# 04_-Connector.net
KiCad netlist of a schematic drawn in Altium Designer
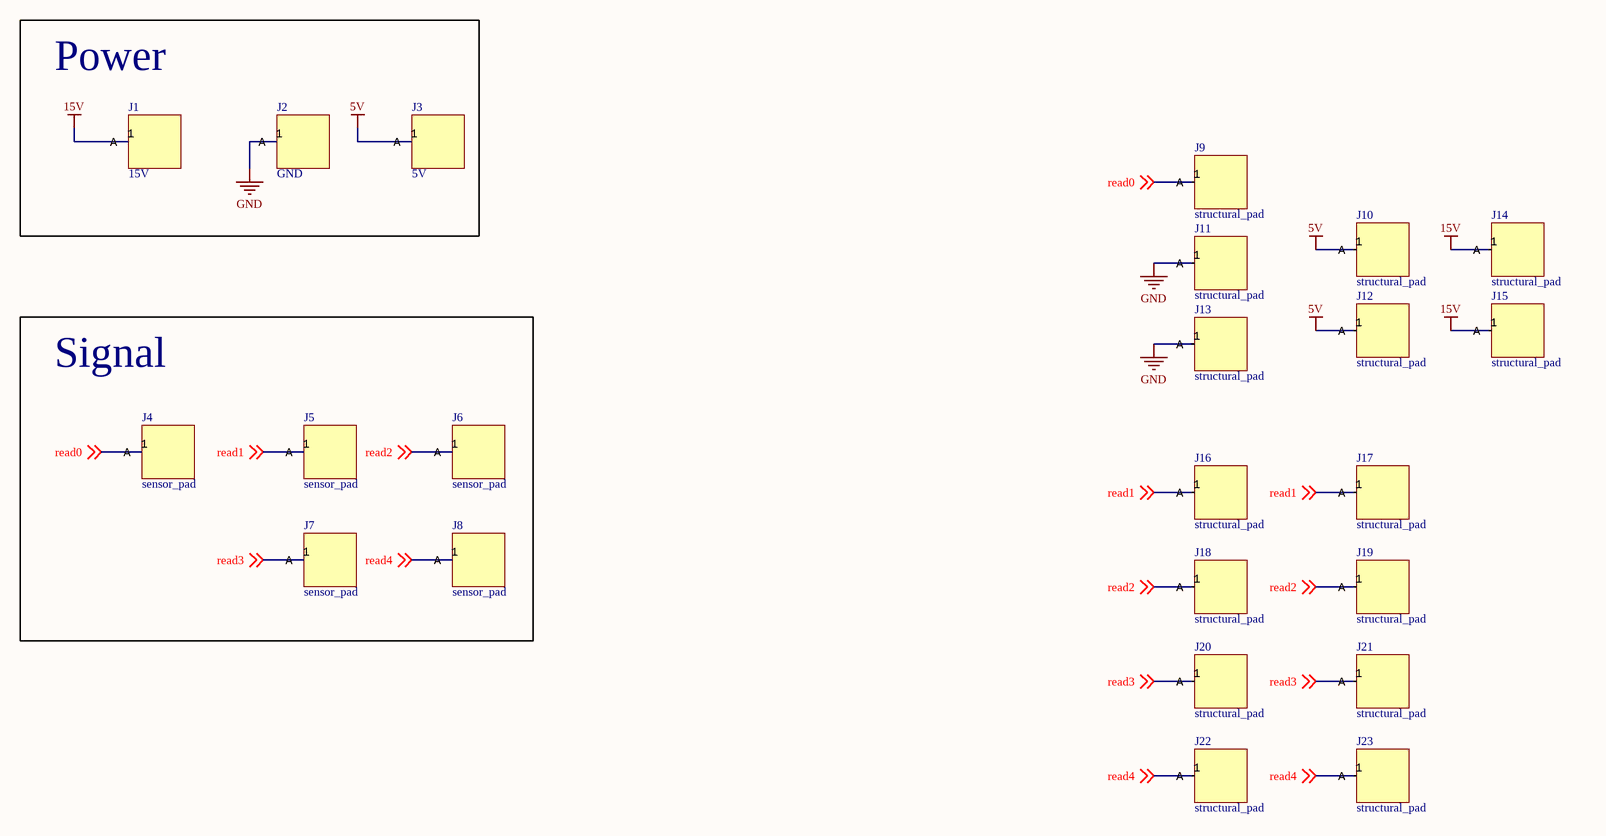
[diagram p0: [04]-Connector.SchDoc]

(export (version "E")
  (design (tool "Eeschema 10.0.6"))
  (components
    (comp (ref "J1") (value "15V") (footprint "PIN") (libsource (lib "Schlib1") (part "15V")))
    (comp (ref "J2") (value "GND") (footprint "PIN") (libsource (lib "Schlib1") (part "GND")))
    (comp (ref "J3") (value "5V") (footprint "PIN") (libsource (lib "Schlib1") (part "15V")))
    (comp (ref "J4") (value "sensor_pad") (footprint "PIN") (libsource (lib "Schlib1") (part "sensor_pad")))
    (comp (ref "J5") (value "sensor_pad") (footprint "PIN") (libsource (lib "Schlib1") (part "sensor_pad")))
    (comp (ref "J6") (value "sensor_pad") (footprint "PIN") (libsource (lib "Schlib1") (part "sensor_pad")))
    (comp (ref "J7") (value "sensor_pad") (footprint "PIN") (libsource (lib "Schlib1") (part "sensor_pad")))
    (comp (ref "J8") (value "sensor_pad") (footprint "PIN") (libsource (lib "Schlib1") (part "sensor_pad")))
    (comp (ref "J9")
      (value "structural_pad")
      (footprint "structural_pad")
      (libsource (lib "Schlib1") (part "structural_pad"))
    )
    (comp (ref "J10")
      (value "structural_pad")
      (footprint "structural_pad")
      (libsource (lib "Schlib1") (part "structural_pad"))
    )
    (comp (ref "J11")
      (value "structural_pad")
      (footprint "structural_pad")
      (libsource (lib "Schlib1") (part "structural_pad"))
    )
    (comp (ref "J12")
      (value "structural_pad")
      (footprint "structural_pad")
      (libsource (lib "Schlib1") (part "structural_pad"))
    )
    (comp (ref "J13")
      (value "structural_pad")
      (footprint "structural_pad")
      (libsource (lib "Schlib1") (part "structural_pad"))
    )
    (comp (ref "J14")
      (value "structural_pad")
      (footprint "structural_pad")
      (libsource (lib "Schlib1") (part "structural_pad"))
    )
    (comp (ref "J15")
      (value "structural_pad")
      (footprint "structural_pad")
      (libsource (lib "Schlib1") (part "structural_pad"))
    )
    (comp (ref "J16")
      (value "structural_pad")
      (footprint "structural_pad")
      (libsource (lib "Schlib1") (part "structural_pad"))
    )
    (comp (ref "J17")
      (value "structural_pad")
      (footprint "structural_pad")
      (libsource (lib "Schlib1") (part "structural_pad"))
    )
    (comp (ref "J18")
      (value "structural_pad")
      (footprint "structural_pad")
      (libsource (lib "Schlib1") (part "structural_pad"))
    )
    (comp (ref "J19")
      (value "structural_pad")
      (footprint "structural_pad")
      (libsource (lib "Schlib1") (part "structural_pad"))
    )
    (comp (ref "J20")
      (value "structural_pad")
      (footprint "structural_pad")
      (libsource (lib "Schlib1") (part "structural_pad"))
    )
    (comp (ref "J21")
      (value "structural_pad")
      (footprint "structural_pad")
      (libsource (lib "Schlib1") (part "structural_pad"))
    )
    (comp (ref "J22")
      (value "structural_pad")
      (footprint "structural_pad")
      (libsource (lib "Schlib1") (part "structural_pad"))
    )
    (comp (ref "J23")
      (value "structural_pad")
      (footprint "structural_pad")
      (libsource (lib "Schlib1") (part "structural_pad"))
    )
  )
  (nets
    (net (code "1") (name "5V") (class "Default")
      (node (ref "J10") (pin "1") (pinfunction "A_1") (pintype "passive"))
      (node (ref "J12") (pin "1") (pinfunction "A_1") (pintype "passive"))
      (node (ref "J3") (pin "1") (pinfunction "A_1") (pintype "passive"))
    )
    (net (code "2") (name "15V") (class "Default")
      (node (ref "J1") (pin "1") (pinfunction "A_1") (pintype "passive"))
      (node (ref "J14") (pin "1") (pinfunction "A_1") (pintype "passive"))
      (node (ref "J15") (pin "1") (pinfunction "A_1") (pintype "passive"))
    )
    (net (code "3") (name "GND") (class "Default")
      (node (ref "J11") (pin "1") (pinfunction "A_1") (pintype "passive"))
      (node (ref "J13") (pin "1") (pinfunction "A_1") (pintype "passive"))
      (node (ref "J2") (pin "1") (pinfunction "A_1") (pintype "passive"))
    )
    (net (code "4") (name "read0") (class "Default")
      (node (ref "J4") (pin "1") (pinfunction "A_1") (pintype "passive"))
      (node (ref "J9") (pin "1") (pinfunction "A_1") (pintype "passive"))
    )
    (net (code "5") (name "read1") (class "Default")
      (node (ref "J16") (pin "1") (pinfunction "A_1") (pintype "passive"))
      (node (ref "J17") (pin "1") (pinfunction "A_1") (pintype "passive"))
      (node (ref "J5") (pin "1") (pinfunction "A_1") (pintype "passive"))
    )
    (net (code "6") (name "read2") (class "Default")
      (node (ref "J18") (pin "1") (pinfunction "A_1") (pintype "passive"))
      (node (ref "J19") (pin "1") (pinfunction "A_1") (pintype "passive"))
      (node (ref "J6") (pin "1") (pinfunction "A_1") (pintype "passive"))
    )
    (net (code "7") (name "read3") (class "Default")
      (node (ref "J20") (pin "1") (pinfunction "A_1") (pintype "passive"))
      (node (ref "J21") (pin "1") (pinfunction "A_1") (pintype "passive"))
      (node (ref "J7") (pin "1") (pinfunction "A_1") (pintype "passive"))
    )
    (net (code "8") (name "read4") (class "Default")
      (node (ref "J22") (pin "1") (pinfunction "A_1") (pintype "passive"))
      (node (ref "J23") (pin "1") (pinfunction "A_1") (pintype "passive"))
      (node (ref "J8") (pin "1") (pinfunction "A_1") (pintype "passive"))
    )
  )
)
